# Harness.net
KiCad netlist of a schematic drawn in Altium Designer
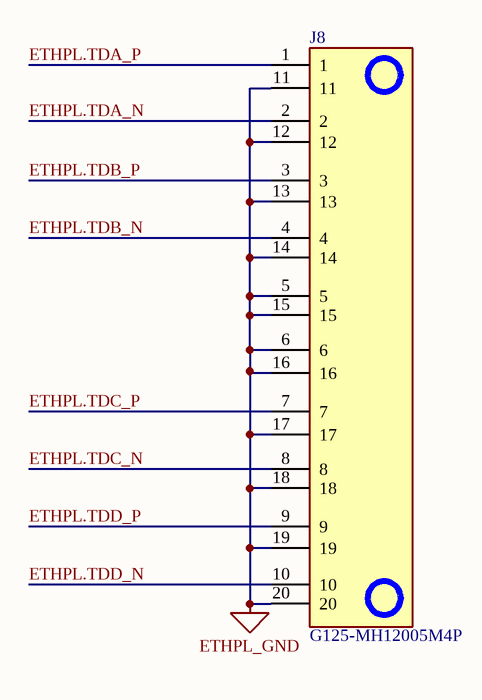
[diagram p0: Harness.SchDoc]

(export (version "E")
  (design (tool "Eeschema 10.0.6"))
  (components
    (comp (ref "J8")
      (value "G125-MH12005M4P")
      (footprint "SamacSys:G125-MH12005M4P_1")
      (description "Connector")
      (fields (field (name "MOUSER PART NUMBER") "855-G125MH1205M4PM4P"))
      (libsource (lib "STeRG-Passives-Standard") (part "G125-MH12005M4P"))
    )
  )
  (nets
    (net (code "1") (name "/ETHPL.TDA_N") (class "Default")
      (node (ref "J8") (pin "2") (pinfunction "2_2") (pintype "passive"))
    )
    (net (code "2") (name "/ETHPL.TDA_P") (class "Default")
      (node (ref "J8") (pin "1") (pinfunction "1_1") (pintype "passive"))
    )
    (net (code "3") (name "/ETHPL.TDB_N") (class "Default")
      (node (ref "J8") (pin "4") (pinfunction "4_4") (pintype "passive"))
    )
    (net (code "4") (name "/ETHPL.TDB_P") (class "Default")
      (node (ref "J8") (pin "3") (pinfunction "3_3") (pintype "passive"))
    )
    (net (code "5") (name "/ETHPL.TDC_N") (class "Default")
      (node (ref "J8") (pin "8") (pinfunction "8_8") (pintype "passive"))
    )
    (net (code "6") (name "/ETHPL.TDC_P") (class "Default")
      (node (ref "J8") (pin "7") (pinfunction "7_7") (pintype "passive"))
    )
    (net (code "7") (name "/ETHPL.TDD_N") (class "Default")
      (node (ref "J8") (pin "10") (pinfunction "10_10") (pintype "passive"))
    )
    (net (code "8") (name "/ETHPL.TDD_P") (class "Default")
      (node (ref "J8") (pin "9") (pinfunction "9_9") (pintype "passive"))
    )
    (net (code "9") (name "ETHPL_GND") (class "Default")
      (node (ref "J8") (pin "11") (pinfunction "11_11") (pintype "passive"))
      (node (ref "J8") (pin "12") (pinfunction "12_12") (pintype "passive"))
      (node (ref "J8") (pin "13") (pinfunction "13_13") (pintype "passive"))
      (node (ref "J8") (pin "14") (pinfunction "14_14") (pintype "passive"))
      (node (ref "J8") (pin "15") (pinfunction "15_15") (pintype "passive"))
      (node (ref "J8") (pin "16") (pinfunction "16_16") (pintype "passive"))
      (node (ref "J8") (pin "17") (pinfunction "17_17") (pintype "passive"))
      (node (ref "J8") (pin "18") (pinfunction "18_18") (pintype "passive"))
      (node (ref "J8") (pin "19") (pinfunction "19_19") (pintype "passive"))
      (node (ref "J8") (pin "20") (pinfunction "20_20") (pintype "passive"))
      (node (ref "J8") (pin "5") (pinfunction "5_5") (pintype "passive"))
      (node (ref "J8") (pin "6") (pinfunction "6_6") (pintype "passive"))
    )
  )
)
